# KeyBoard-RP2040_P1.net
KiCad netlist of a schematic drawn in Altium Designer
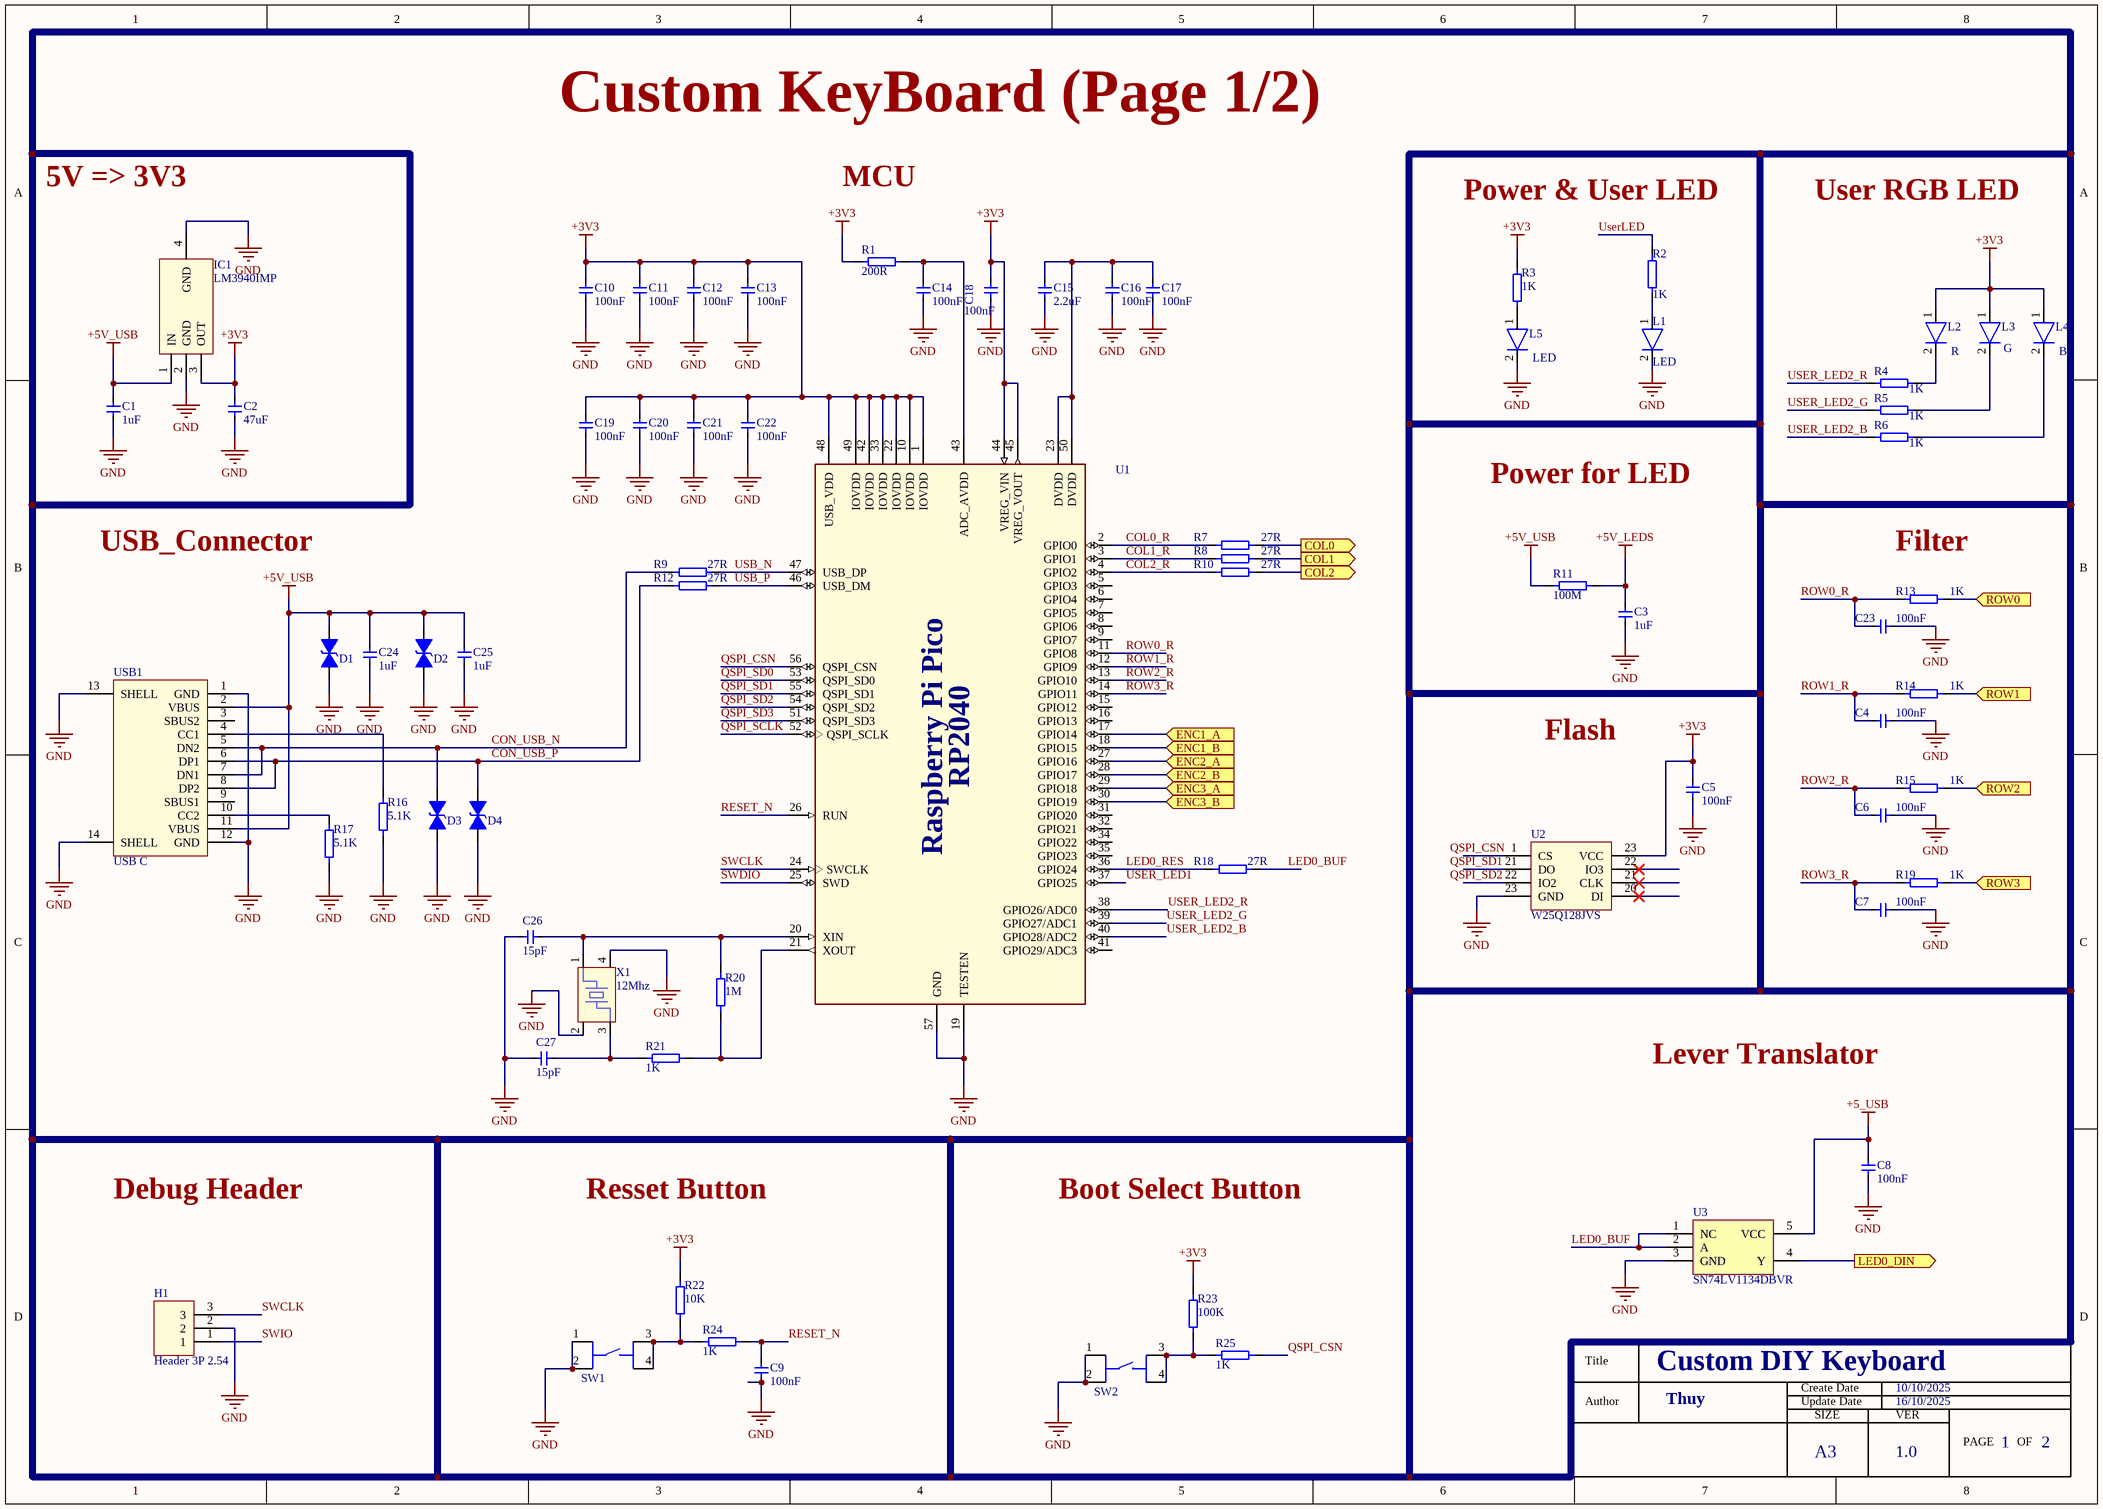
[diagram p0: KeyBoard-RP2040_P1.SchDoc]

(export (version "E")
  (design (tool "Eeschema 10.0.6"))
  (components
    (comp (ref "C1")
      (value "1uF")
      (footprint "C 0.79 0.54")
      (description "SMD 0402")
      (libsource (lib "SCHLib") (part "CAP 1uF"))
    )
    (comp (ref "C2")
      (value "47uF")
      (footprint "C 1.485 1.728")
      (description "SMD")
      (libsource (lib "SCHLib") (part "CAP 47uF"))
    )
    (comp (ref "C3")
      (value "1uF")
      (footprint "C 0.79 0.54")
      (description "SMD 0402")
      (libsource (lib "SCHLib") (part "CAP 1uF"))
    )
    (comp (ref "C4")
      (value "100nF")
      (footprint "C 0.79 0.54")
      (description "SMD")
      (libsource (lib "SCHLib") (part "CAP 100nF"))
    )
    (comp (ref "C5")
      (value "100nF")
      (footprint "C 0.79 0.54")
      (description "SMD")
      (libsource (lib "SCHLib") (part "CAP 100nF"))
    )
    (comp (ref "C6")
      (value "100nF")
      (footprint "C 0.79 0.54")
      (description "SMD")
      (libsource (lib "SCHLib") (part "CAP 100nF"))
    )
    (comp (ref "C7")
      (value "100nF")
      (footprint "C 0.79 0.54")
      (description "SMD")
      (libsource (lib "SCHLib") (part "CAP 100nF"))
    )
    (comp (ref "C8")
      (value "100nF")
      (footprint "C 0.79 0.54")
      (description "SMD")
      (libsource (lib "SCHLib") (part "CAP 100nF"))
    )
    (comp (ref "C9")
      (value "100nF")
      (footprint "C 0.79 0.54")
      (description "SMD")
      (libsource (lib "SCHLib") (part "CAP 100nF"))
    )
    (comp (ref "C10")
      (value "100nF")
      (footprint "C 0.79 0.54")
      (description "SMD")
      (libsource (lib "SCHLib") (part "CAP 100nF"))
    )
    (comp (ref "C11")
      (value "100nF")
      (footprint "C 0.79 0.54")
      (description "SMD")
      (libsource (lib "SCHLib") (part "CAP 100nF"))
    )
    (comp (ref "C12")
      (value "100nF")
      (footprint "C 0.79 0.54")
      (description "SMD")
      (libsource (lib "SCHLib") (part "CAP 100nF"))
    )
    (comp (ref "C13")
      (value "100nF")
      (footprint "C 0.79 0.54")
      (description "SMD")
      (libsource (lib "SCHLib") (part "CAP 100nF"))
    )
    (comp (ref "C14")
      (value "100nF")
      (footprint "C 0.79 0.54")
      (description "SMD")
      (libsource (lib "SCHLib") (part "CAP 100nF"))
    )
    (comp (ref "C15")
      (value "2.2uF")
      (footprint "C 0.79 0.54")
      (description "SMD")
      (libsource (lib "SCHLib") (part "CAP 2.2uF"))
    )
    (comp (ref "C16")
      (value "100nF")
      (footprint "C 0.79 0.54")
      (description "SMD")
      (libsource (lib "SCHLib") (part "CAP 100nF"))
    )
    (comp (ref "C17")
      (value "100nF")
      (footprint "C 0.79 0.54")
      (description "SMD")
      (libsource (lib "SCHLib") (part "CAP 100nF"))
    )
    (comp (ref "C18")
      (value "100nF")
      (footprint "C 0.79 0.54")
      (description "SMD")
      (libsource (lib "SCHLib") (part "CAP 100nF"))
    )
    (comp (ref "C19")
      (value "100nF")
      (footprint "C 0.79 0.54")
      (description "SMD")
      (libsource (lib "SCHLib") (part "CAP 100nF"))
    )
    (comp (ref "C20")
      (value "100nF")
      (footprint "C 0.79 0.54")
      (description "SMD")
      (libsource (lib "SCHLib") (part "CAP 100nF"))
    )
    (comp (ref "C21")
      (value "100nF")
      (footprint "C 0.79 0.54")
      (description "SMD")
      (libsource (lib "SCHLib") (part "CAP 100nF"))
    )
    (comp (ref "C22")
      (value "100nF")
      (footprint "C 0.79 0.54")
      (description "SMD")
      (libsource (lib "SCHLib") (part "CAP 100nF"))
    )
    (comp (ref "C23")
      (value "100nF")
      (footprint "C 0.79 0.54")
      (description "SMD")
      (libsource (lib "SCHLib") (part "CAP 100nF"))
    )
    (comp (ref "C24")
      (value "1uF")
      (footprint "C 0.79 0.54")
      (description "SMD 0402")
      (libsource (lib "SCHLib") (part "CAP 1uF"))
    )
    (comp (ref "C25")
      (value "1uF")
      (footprint "C 0.79 0.54")
      (description "SMD 0402")
      (libsource (lib "SCHLib") (part "CAP 1uF"))
    )
    (comp (ref "C26")
      (value "15pF")
      (footprint "C 0.79 0.54")
      (description "SMD")
      (libsource (lib "SCHLib") (part "CAP 15pF"))
    )
    (comp (ref "C27")
      (value "15pF")
      (footprint "C 0.79 0.54")
      (description "SMD")
      (libsource (lib "SCHLib") (part "CAP 15pF"))
    )
    (comp (ref "D1")
      (value "ESD GG0402052R542P")
      (footprint "D 0.6")
      (description "SMD")
      (libsource (lib "SCHLib") (part "ESD GG0402052R542P"))
    )
    (comp (ref "D2")
      (value "ESD GG0402052R542P")
      (footprint "D 0.6")
      (description "SMD")
      (libsource (lib "SCHLib") (part "ESD GG0402052R542P"))
    )
    (comp (ref "D3")
      (value "ESD GG0402052R542P")
      (footprint "D 0.6")
      (description "SMD")
      (libsource (lib "SCHLib") (part "ESD GG0402052R542P"))
    )
    (comp (ref "D4")
      (value "ESD GG0402052R542P")
      (footprint "D 0.6")
      (description "SMD")
      (libsource (lib "SCHLib") (part "ESD GG0402052R542P"))
    )
    (comp (ref "H1")
      (value "Header 3P 2.54")
      (footprint "Header 1x3")
      (description "THT")
      (libsource (lib "SCHLib") (part "Header 1x3"))
    )
    (comp (ref "IC1")
      (value "LM3940IMP")
      (footprint "LM39")
      (description "SOP ¦ 5v->3v3 ¦")
      (libsource (lib "SCHLib") (part "LM3940IMP"))
    )
    (comp (ref "L1") (value "LED") (footprint "LED") (libsource (lib "SCHLib") (part "LED2")))
    (comp (ref "L2") (value "R") (footprint "LED") (libsource (lib "SCHLib") (part "LED2")))
    (comp (ref "L3") (value "G") (footprint "LED") (libsource (lib "SCHLib") (part "LED2")))
    (comp (ref "L4") (value "B") (footprint "LED") (libsource (lib "SCHLib") (part "LED2")))
    (comp (ref "L5") (value "LED") (footprint "LED") (libsource (lib "SCHLib") (part "LED2")))
    (comp (ref "R1")
      (value "200R")
      (footprint "SMD 0.566 0.54")
      (description "SMD")
      (libsource (lib "SCHLib") (part "RES 200R"))
    )
    (comp (ref "R2")
      (value "1K")
      (footprint "SMD 0.566 0.54")
      (description "SMD")
      (libsource (lib "") (part "RES 1K_2"))
    )
    (comp (ref "R3")
      (value "1K")
      (footprint "SMD 0.566 0.54")
      (description "SMD")
      (libsource (lib "") (part "RES 1K_2"))
    )
    (comp (ref "R4")
      (value "1K")
      (footprint "SMD 0.566 0.54")
      (description "SMD")
      (libsource (lib "SCHLib") (part "RES 1K"))
    )
    (comp (ref "R5")
      (value "1K")
      (footprint "SMD 0.566 0.54")
      (description "SMD")
      (libsource (lib "SCHLib") (part "RES 1K"))
    )
    (comp (ref "R6")
      (value "1K")
      (footprint "SMD 0.566 0.54")
      (description "SMD")
      (libsource (lib "SCHLib") (part "RES 1K"))
    )
    (comp (ref "R7")
      (value "27R")
      (footprint "SMD 0.566 0.54")
      (description "SMD")
      (libsource (lib "SCHLib") (part "Res 27R"))
    )
    (comp (ref "R8")
      (value "27R")
      (footprint "SMD 0.566 0.54")
      (description "SMD")
      (libsource (lib "SCHLib") (part "Res 27R"))
    )
    (comp (ref "R9")
      (value "27R")
      (footprint "SMD 0.566 0.54")
      (description "SMD")
      (libsource (lib "SCHLib") (part "Res 27R"))
    )
    (comp (ref "R10")
      (value "27R")
      (footprint "SMD 0.566 0.54")
      (description "SMD")
      (libsource (lib "SCHLib") (part "Res 27R"))
    )
    (comp (ref "R11")
      (value "100M")
      (footprint "SMD 0.566 0.54")
      (description "SMD")
      (libsource (lib "SCHLib") (part "RES 100M"))
    )
    (comp (ref "R12")
      (value "27R")
      (footprint "SMD 0.566 0.54")
      (description "SMD")
      (libsource (lib "SCHLib") (part "Res 27R"))
    )
    (comp (ref "R13")
      (value "1K")
      (footprint "SMD 0.566 0.54")
      (description "SMD")
      (libsource (lib "") (part "RES 1K_1"))
    )
    (comp (ref "R14")
      (value "1K")
      (footprint "SMD 0.566 0.54")
      (description "SMD")
      (libsource (lib "") (part "RES 1K_1"))
    )
    (comp (ref "R15")
      (value "1K")
      (footprint "SMD 0.566 0.54")
      (description "SMD")
      (libsource (lib "") (part "RES 1K_1"))
    )
    (comp (ref "R16")
      (value "5.1K")
      (footprint "SMD 0.566 0.54")
      (description "SMD")
      (libsource (lib "SCHLib") (part "RES 5.1K"))
    )
    (comp (ref "R17")
      (value "5.1K")
      (footprint "SMD 0.566 0.54")
      (description "SMD")
      (libsource (lib "SCHLib") (part "RES 5.1K"))
    )
    (comp (ref "R18")
      (value "27R")
      (footprint "SMD 0.566 0.54")
      (description "SMD")
      (libsource (lib "SCHLib") (part "Res 27R"))
    )
    (comp (ref "R19")
      (value "1K")
      (footprint "SMD 0.566 0.54")
      (description "SMD")
      (libsource (lib "") (part "RES 1K_1"))
    )
    (comp (ref "R20")
      (value "1M")
      (footprint "SMD 0.566 0.54")
      (description "SMD")
      (libsource (lib "SCHLib") (part "RES 1M"))
    )
    (comp (ref "R21")
      (value "1K")
      (footprint "SMD 0.566 0.54")
      (description "SMD")
      (libsource (lib "") (part "RES 1K_1"))
    )
    (comp (ref "R22")
      (value "10K")
      (footprint "SMD 0.566 0.54")
      (description "SMD")
      (libsource (lib "SCHLib") (part "RES 10K"))
    )
    (comp (ref "R23")
      (value "100K")
      (footprint "SMD 0.566 0.54")
      (description "SMD")
      (libsource (lib "SCHLib") (part "RES 100K"))
    )
    (comp (ref "R24")
      (value "1K")
      (footprint "SMD 0.566 0.54")
      (description "SMD")
      (libsource (lib "") (part "RES 1K_1"))
    )
    (comp (ref "R25")
      (value "1K")
      (footprint "SMD 0.566 0.54")
      (description "SMD")
      (libsource (lib "") (part "RES 1K_1"))
    )
    (comp (ref "SW1")
      (value "BUTTON")
      (footprint "Button")
      (description "SMD")
      (libsource (lib "SCHLib") (part "BUTTON"))
    )
    (comp (ref "SW2")
      (value "BUTTON")
      (footprint "Button")
      (description "SMD")
      (libsource (lib "SCHLib") (part "BUTTON"))
    )
    (comp (ref "U1")
      (value "RP2040")
      (footprint "RP2040")
      (description "RP2040 chip for Raspberry Pi Pico - ARM® Cortex®-M0+ MCU 32-Bit")
      (libsource (lib "SCHLib") (part "Rasberry Pi Pico-RP2040"))
    )
    (comp (ref "U2")
      (value "W25Q128JVS")
      (footprint "W25Q128JVS")
      (description "SMD")
      (libsource (lib "SCHLib") (part "W25Q128JVS"))
    )
    (comp (ref "U3") (value "SN74LV1134DBVR") (libsource (lib "SCHLib") (part "SN74LV1134DBVR")))
    (comp (ref "USB1") (value "USB C") (footprint "USB-C") (libsource (lib "SCHLib") (part "USB C")))
    (comp (ref "X1")
      (value "12Mhz")
      (footprint "ABM8")
      (description "SMD")
      (libsource (lib "SCHLib") (part "Crystal ABM8-272-T3"))
    )
  )
  (nets
    (net (code "1") (name "+3V3") (class "Default")
      (node (ref "C10") (pin "2") (pinfunction "2_2") (pintype "passive"))
      (node (ref "C11") (pin "2") (pinfunction "2_2") (pintype "passive"))
      (node (ref "C12") (pin "2") (pinfunction "2_2") (pintype "passive"))
      (node (ref "C13") (pin "2") (pinfunction "2_2") (pintype "passive"))
      (node (ref "C18") (pin "2") (pinfunction "2_2") (pintype "passive"))
      (node (ref "C19") (pin "2") (pinfunction "2_2") (pintype "passive"))
      (node (ref "C2") (pin "2") (pinfunction "2_2") (pintype "passive"))
      (node (ref "C20") (pin "2") (pinfunction "2_2") (pintype "passive"))
      (node (ref "C21") (pin "2") (pinfunction "2_2") (pintype "passive"))
      (node (ref "C22") (pin "2") (pinfunction "2_2") (pintype "passive"))
      (node (ref "C5") (pin "2") (pinfunction "2_2") (pintype "passive"))
      (node (ref "IC1") (pin "3") (pinfunction "OUT_3") (pintype "passive"))
      (node (ref "L2") (pin "1") (pinfunction "1_1") (pintype "passive"))
      (node (ref "L3") (pin "1") (pinfunction "1_1") (pintype "passive"))
      (node (ref "L4") (pin "1") (pinfunction "1_1") (pintype "passive"))
      (node (ref "R1") (pin "1") (pinfunction "1_1") (pintype "passive"))
      (node (ref "R22") (pin "2") (pinfunction "2_2") (pintype "passive"))
      (node (ref "R23") (pin "2") (pinfunction "2_2") (pintype "passive"))
      (node (ref "R3") (pin "2") (pinfunction "2_2") (pintype "passive"))
      (node (ref "U1") (pin "1") (pinfunction "IOVDD_1") (pintype "power_in"))
      (node (ref "U1") (pin "10") (pinfunction "IOVDD_10") (pintype "power_in"))
      (node (ref "U1") (pin "22") (pinfunction "IOVDD_22") (pintype "power_in"))
      (node (ref "U1") (pin "33") (pinfunction "IOVDD_33") (pintype "power_in"))
      (node (ref "U1") (pin "42") (pinfunction "IOVDD_42") (pintype "power_in"))
      (node (ref "U1") (pin "44") (pinfunction "VREG_VIN_44") (pintype "input"))
      (node (ref "U1") (pin "45") (pinfunction "VREG_VOUT_45") (pintype "output"))
      (node (ref "U1") (pin "48") (pinfunction "USB_VDD_48") (pintype "power_in"))
      (node (ref "U1") (pin "49") (pinfunction "IOVDD_49") (pintype "power_in"))
      (node (ref "U2") (pin "23") (pinfunction "VCC_23") (pintype "passive"))
    )
    (net (code "2") (name "+5V_LEDS") (class "Default")
      (node (ref "C3") (pin "2") (pinfunction "2_2") (pintype "passive"))
      (node (ref "R11") (pin "2") (pinfunction "2_2") (pintype "passive"))
    )
    (net (code "3") (name "+5V_USB") (class "Default")
      (node (ref "C1") (pin "2") (pinfunction "2_2") (pintype "passive"))
      (node (ref "C24") (pin "2") (pinfunction "2_2") (pintype "passive"))
      (node (ref "C25") (pin "2") (pinfunction "2_2") (pintype "passive"))
      (node (ref "D1") (pin "2") (pinfunction "2_2") (pintype "passive"))
      (node (ref "D2") (pin "2") (pinfunction "2_2") (pintype "passive"))
      (node (ref "IC1") (pin "1") (pinfunction "IN_1") (pintype "passive"))
      (node (ref "R11") (pin "1") (pinfunction "1_1") (pintype "passive"))
      (node (ref "USB1") (pin "11") (pinfunction "VBUS_11") (pintype "passive"))
      (node (ref "USB1") (pin "2") (pinfunction "VBUS_2") (pintype "passive"))
    )
    (net (code "4") (name "+5_USB") (class "Default")
      (node (ref "C8") (pin "2") (pinfunction "2_2") (pintype "passive"))
      (node (ref "U3") (pin "5") (pinfunction "VCC_5") (pintype "passive"))
    )
    (net (code "5") (name "/COL0") (class "Default")
      (node (ref "R7") (pin "2") (pinfunction "2_2") (pintype "passive"))
    )
    (net (code "6") (name "/COL0_R") (class "Default")
      (node (ref "R7") (pin "1") (pinfunction "1_1") (pintype "passive"))
      (node (ref "U1") (pin "2") (pinfunction "GPIO0_2") (pintype "bidirectional"))
    )
    (net (code "7") (name "/COL1") (class "Default")
      (node (ref "R8") (pin "2") (pinfunction "2_2") (pintype "passive"))
    )
    (net (code "8") (name "/COL1_R") (class "Default")
      (node (ref "R8") (pin "1") (pinfunction "1_1") (pintype "passive"))
      (node (ref "U1") (pin "3") (pinfunction "GPIO1_3") (pintype "bidirectional"))
    )
    (net (code "9") (name "/COL2") (class "Default")
      (node (ref "R10") (pin "2") (pinfunction "2_2") (pintype "passive"))
    )
    (net (code "10") (name "/COL2_R") (class "Default")
      (node (ref "R10") (pin "1") (pinfunction "1_1") (pintype "passive"))
      (node (ref "U1") (pin "4") (pinfunction "GPIO2_4") (pintype "bidirectional"))
    )
    (net (code "11") (name "/CON_USB_N") (class "Default")
      (node (ref "D3") (pin "2") (pinfunction "2_2") (pintype "passive"))
      (node (ref "R9") (pin "1") (pinfunction "1_1") (pintype "passive"))
      (node (ref "USB1") (pin "5") (pinfunction "DN2_5") (pintype "passive"))
      (node (ref "USB1") (pin "7") (pinfunction "DN1_7") (pintype "passive"))
    )
    (net (code "12") (name "/CON_USB_P") (class "Default")
      (node (ref "D4") (pin "2") (pinfunction "2_2") (pintype "passive"))
      (node (ref "R12") (pin "1") (pinfunction "1_1") (pintype "passive"))
      (node (ref "USB1") (pin "6") (pinfunction "DP1_6") (pintype "passive"))
      (node (ref "USB1") (pin "8") (pinfunction "DP2_8") (pintype "passive"))
    )
    (net (code "13") (name "/ENC1_A") (class "Default")
      (node (ref "U1") (pin "17") (pinfunction "GPIO14_17") (pintype "bidirectional"))
    )
    (net (code "14") (name "/ENC1_B") (class "Default")
      (node (ref "U1") (pin "18") (pinfunction "GPIO15_18") (pintype "bidirectional"))
    )
    (net (code "15") (name "/ENC2_A") (class "Default")
      (node (ref "U1") (pin "27") (pinfunction "GPIO16_27") (pintype "bidirectional"))
    )
    (net (code "16") (name "/ENC2_B") (class "Default")
      (node (ref "U1") (pin "28") (pinfunction "GPIO17_28") (pintype "bidirectional"))
    )
    (net (code "17") (name "/ENC3_A") (class "Default")
      (node (ref "U1") (pin "29") (pinfunction "GPIO18_29") (pintype "bidirectional"))
    )
    (net (code "18") (name "/ENC3_B") (class "Default")
      (node (ref "U1") (pin "30") (pinfunction "GPIO19_30") (pintype "bidirectional"))
    )
    (net (code "19") (name "/LED0_BUF") (class "Default")
      (node (ref "R18") (pin "2") (pinfunction "2_2") (pintype "passive"))
      (node (ref "U3") (pin "1") (pinfunction "NC_1") (pintype "passive"))
      (node (ref "U3") (pin "2") (pinfunction "A_2") (pintype "passive"))
    )
    (net (code "20") (name "/LED0_DIN") (class "Default")
      (node (ref "U3") (pin "4") (pinfunction "Y_4") (pintype "passive"))
    )
    (net (code "21") (name "/LED0_RES") (class "Default")
      (node (ref "R18") (pin "1") (pinfunction "1_1") (pintype "passive"))
      (node (ref "U1") (pin "36") (pinfunction "GPIO24_36") (pintype "bidirectional"))
    )
    (net (code "22") (name "/QSPI_CSN") (class "Default")
      (node (ref "R25") (pin "2") (pinfunction "2_2") (pintype "passive"))
      (node (ref "U1") (pin "56") (pinfunction "QSPI_CSN_56") (pintype "bidirectional"))
    )
    (net (code "23") (name "/QSPI_SCLK") (class "Default")
      (node (ref "U1") (pin "52") (pinfunction "QSPI_SCLK_52") (pintype "bidirectional"))
    )
    (net (code "24") (name "/QSPI_SD0") (class "Default")
      (node (ref "U1") (pin "53") (pinfunction "QSPI_SD0_53") (pintype "bidirectional"))
    )
    (net (code "25") (name "/QSPI_SD1") (class "Default")
      (node (ref "U1") (pin "55") (pinfunction "QSPI_SD1_55") (pintype "bidirectional"))
    )
    (net (code "26") (name "/QSPI_SD2") (class "Default")
      (node (ref "U1") (pin "54") (pinfunction "QSPI_SD2_54") (pintype "bidirectional"))
    )
    (net (code "27") (name "/QSPI_SD3") (class "Default")
      (node (ref "U1") (pin "51") (pinfunction "QSPI_SD3_51") (pintype "bidirectional"))
    )
    (net (code "28") (name "/RESET_N") (class "Default")
      (node (ref "C9") (pin "2") (pinfunction "2_2") (pintype "passive"))
      (node (ref "R24") (pin "2") (pinfunction "2_2") (pintype "passive"))
      (node (ref "U1") (pin "26") (pinfunction "RUN_26") (pintype "input"))
    )
    (net (code "29") (name "/ROW0") (class "Default")
      (node (ref "R13") (pin "2") (pinfunction "2_2") (pintype "passive"))
    )
    (net (code "30") (name "/ROW0_R") (class "Default")
      (node (ref "C23") (pin "2") (pinfunction "2_2") (pintype "passive"))
      (node (ref "R13") (pin "1") (pinfunction "1_1") (pintype "passive"))
      (node (ref "U1") (pin "11") (pinfunction "GPIO8_11") (pintype "bidirectional"))
    )
    (net (code "31") (name "/ROW1") (class "Default")
      (node (ref "R14") (pin "2") (pinfunction "2_2") (pintype "passive"))
    )
    (net (code "32") (name "/ROW1_R") (class "Default")
      (node (ref "C4") (pin "2") (pinfunction "2_2") (pintype "passive"))
      (node (ref "R14") (pin "1") (pinfunction "1_1") (pintype "passive"))
      (node (ref "U1") (pin "12") (pinfunction "GPIO9_12") (pintype "bidirectional"))
    )
    (net (code "33") (name "/ROW2") (class "Default")
      (node (ref "R15") (pin "2") (pinfunction "2_2") (pintype "passive"))
    )
    (net (code "34") (name "/ROW2_R") (class "Default")
      (node (ref "C6") (pin "2") (pinfunction "2_2") (pintype "passive"))
      (node (ref "R15") (pin "1") (pinfunction "1_1") (pintype "passive"))
      (node (ref "U1") (pin "13") (pinfunction "GPIO10_13") (pintype "bidirectional"))
    )
    (net (code "35") (name "/ROW3") (class "Default")
      (node (ref "R19") (pin "2") (pinfunction "2_2") (pintype "passive"))
    )
    (net (code "36") (name "/ROW3_R") (class "Default")
      (node (ref "C7") (pin "2") (pinfunction "2_2") (pintype "passive"))
      (node (ref "R19") (pin "1") (pinfunction "1_1") (pintype "passive"))
      (node (ref "U1") (pin "14") (pinfunction "GPIO11_14") (pintype "bidirectional"))
    )
    (net (code "37") (name "/SWCLK") (class "Default")
      (node (ref "H1") (pin "3") (pinfunction "3_3") (pintype "passive"))
      (node (ref "U1") (pin "24") (pinfunction "SWCLK_24") (pintype "input"))
    )
    (net (code "38") (name "/SWDIO") (class "Default")
      (node (ref "U1") (pin "25") (pinfunction "SWD_25") (pintype "bidirectional"))
    )
    (net (code "39") (name "/SWIO") (class "Default")
      (node (ref "H1") (pin "1") (pinfunction "1_1") (pintype "passive"))
    )
    (net (code "40") (name "/USB_N") (class "Default")
      (node (ref "R9") (pin "2") (pinfunction "2_2") (pintype "passive"))
      (node (ref "U1") (pin "47") (pinfunction "USB_DP_47") (pintype "bidirectional"))
    )
    (net (code "41") (name "/USB_P") (class "Default")
      (node (ref "R12") (pin "2") (pinfunction "2_2") (pintype "passive"))
      (node (ref "U1") (pin "46") (pinfunction "USB_DM_46") (pintype "bidirectional"))
    )
    (net (code "42") (name "/USER_LED1") (class "Default")
      (node (ref "U1") (pin "37") (pinfunction "GPIO25_37") (pintype "bidirectional"))
    )
    (net (code "43") (name "/USER_LED2_B") (class "Default")
      (node (ref "R6") (pin "2") (pinfunction "2_2") (pintype "passive"))
      (node (ref "U1") (pin "40") (pinfunction "GPIO28/ADC2_40") (pintype "bidirectional"))
    )
    (net (code "44") (name "/USER_LED2_G") (class "Default")
      (node (ref "R5") (pin "2") (pinfunction "2_2") (pintype "passive"))
      (node (ref "U1") (pin "39") (pinfunction "GPIO27/ADC1_39") (pintype "bidirectional"))
    )
    (net (code "45") (name "/USER_LED2_R") (class "Default")
      (node (ref "R4") (pin "2") (pinfunction "2_2") (pintype "passive"))
      (node (ref "U1") (pin "38") (pinfunction "GPIO26/ADC0_38") (pintype "bidirectional"))
    )
    (net (code "46") (name "/UserLED") (class "Default")
      (node (ref "R2") (pin "2") (pinfunction "2_2") (pintype "passive"))
    )
    (net (code "47") (name "GND") (class "Default")
      (node (ref "C1") (pin "1") (pinfunction "1_1") (pintype "passive"))
      (node (ref "C10") (pin "1") (pinfunction "1_1") (pintype "passive"))
      (node (ref "C11") (pin "1") (pinfunction "1_1") (pintype "passive"))
      (node (ref "C12") (pin "1") (pinfunction "1_1") (pintype "passive"))
      (node (ref "C13") (pin "1") (pinfunction "1_1") (pintype "passive"))
      (node (ref "C14") (pin "1") (pinfunction "1_1") (pintype "passive"))
      (node (ref "C15") (pin "1") (pinfunction "1_1") (pintype "passive"))
      (node (ref "C16") (pin "1") (pinfunction "1_1") (pintype "passive"))
      (node (ref "C17") (pin "1") (pinfunction "1_1") (pintype "passive"))
      (node (ref "C18") (pin "1") (pinfunction "1_1") (pintype "passive"))
      (node (ref "C19") (pin "1") (pinfunction "1_1") (pintype "passive"))
      (node (ref "C2") (pin "1") (pinfunction "1_1") (pintype "passive"))
      (node (ref "C20") (pin "1") (pinfunction "1_1") (pintype "passive"))
      (node (ref "C21") (pin "1") (pinfunction "1_1") (pintype "passive"))
      (node (ref "C22") (pin "1") (pinfunction "1_1") (pintype "passive"))
      (node (ref "C23") (pin "1") (pinfunction "1_1") (pintype "passive"))
      (node (ref "C24") (pin "1") (pinfunction "1_1") (pintype "passive"))
      (node (ref "C25") (pin "1") (pinfunction "1_1") (pintype "passive"))
      (node (ref "C26") (pin "1") (pinfunction "1_1") (pintype "passive"))
      (node (ref "C27") (pin "1") (pinfunction "1_1") (pintype "passive"))
      (node (ref "C3") (pin "1") (pinfunction "1_1") (pintype "passive"))
      (node (ref "C4") (pin "1") (pinfunction "1_1") (pintype "passive"))
      (node (ref "C5") (pin "1") (pinfunction "1_1") (pintype "passive"))
      (node (ref "C6") (pin "1") (pinfunction "1_1") (pintype "passive"))
      (node (ref "C7") (pin "1") (pinfunction "1_1") (pintype "passive"))
      (node (ref "C8") (pin "1") (pinfunction "1_1") (pintype "passive"))
      (node (ref "C9") (pin "1") (pinfunction "1_1") (pintype "passive"))
      (node (ref "D1") (pin "1") (pinfunction "1_1") (pintype "passive"))
      (node (ref "D2") (pin "1") (pinfunction "1_1") (pintype "passive"))
      (node (ref "D3") (pin "1") (pinfunction "1_1") (pintype "passive"))
      (node (ref "D4") (pin "1") (pinfunction "1_1") (pintype "passive"))
      (node (ref "H1") (pin "2") (pinfunction "2_2") (pintype "passive"))
      (node (ref "IC1") (pin "2") (pinfunction "GND_2") (pintype "passive"))
      (node (ref "IC1") (pin "4") (pinfunction "GND_4") (pintype "passive"))
      (node (ref "L1") (pin "2") (pinfunction "2_2") (pintype "passive"))
      (node (ref "L5") (pin "2") (pinfunction "2_2") (pintype "passive"))
      (node (ref "R16") (pin "1") (pinfunction "1_1") (pintype "passive"))
      (node (ref "R17") (pin "1") (pinfunction "1_1") (pintype "passive"))
      (node (ref "SW1") (pin "1") (pinfunction "1_1") (pintype "passive"))
      (node (ref "SW1") (pin "2") (pinfunction "2_2") (pintype "passive"))
      (node (ref "SW2") (pin "1") (pinfunction "1_1") (pintype "passive"))
      (node (ref "SW2") (pin "2") (pinfunction "2_2") (pintype "passive"))
      (node (ref "U1") (pin "19") (pinfunction "TESTEN_19") (pintype "passive"))
      (node (ref "U1") (pin "57") (pinfunction "GND_57") (pintype "power_in"))
      (node (ref "U2") (pin "23") (pinfunction "GND_23") (pintype "passive"))
      (node (ref "U3") (pin "3") (pinfunction "GND_3") (pintype "passive"))
      (node (ref "USB1") (pin "1") (pinfunction "GND_1") (pintype "passive"))
      (node (ref "USB1") (pin "12") (pinfunction "GND_12") (pintype "passive"))
      (node (ref "USB1") (pin "13") (pinfunction "SHELL_13") (pintype "passive"))
      (node (ref "USB1") (pin "14") (pinfunction "SHELL_14") (pintype "passive"))
      (node (ref "X1") (pin "2") (pinfunction "GND_2") (pintype "passive"))
      (node (ref "X1") (pin "4") (pinfunction "GND_4") (pintype "passive"))
    )
    (net (code "48") (name "Net-(C15-Pad2)") (class "Default")
      (node (ref "C15") (pin "2") (pinfunction "2_2") (pintype "passive"))
      (node (ref "C16") (pin "2") (pinfunction "2_2") (pintype "passive"))
      (node (ref "C17") (pin "2") (pinfunction "2_2") (pintype "passive"))
      (node (ref "U1") (pin "23") (pinfunction "DVDD_23") (pintype "power_in"))
      (node (ref "U1") (pin "50") (pinfunction "DVDD_50") (pintype "power_in"))
    )
    (net (code "49") (name "Net-(C27-Pad2)") (class "Default")
      (node (ref "C27") (pin "2") (pinfunction "2_2") (pintype "passive"))
      (node (ref "R21") (pin "1") (pinfunction "1_1") (pintype "passive"))
      (node (ref "X1") (pin "3") (pinfunction "3_3") (pintype "passive"))
    )
    (net (code "50") (name "Net-(L1-Pad1)") (class "Default")
      (node (ref "L1") (pin "1") (pinfunction "1_1") (pintype "passive"))
      (node (ref "R2") (pin "1") (pinfunction "1_1") (pintype "passive"))
    )
    (net (code "51") (name "Net-(L2-Pad2)") (class "Default")
      (node (ref "L2") (pin "2") (pinfunction "2_2") (pintype "passive"))
      (node (ref "R4") (pin "1") (pinfunction "1_1") (pintype "passive"))
    )
    (net (code "52") (name "Net-(L3-Pad2)") (class "Default")
      (node (ref "L3") (pin "2") (pinfunction "2_2") (pintype "passive"))
      (node (ref "R5") (pin "1") (pinfunction "1_1") (pintype "passive"))
    )
    (net (code "53") (name "Net-(L4-Pad2)") (class "Default")
      (node (ref "L4") (pin "2") (pinfunction "2_2") (pintype "passive"))
      (node (ref "R6") (pin "1") (pinfunction "1_1") (pintype "passive"))
    )
    (net (code "54") (name "Net-(L5-Pad1)") (class "Default")
      (node (ref "L5") (pin "1") (pinfunction "1_1") (pintype "passive"))
      (node (ref "R3") (pin "1") (pinfunction "1_1") (pintype "passive"))
    )
    (net (code "55") (name "Net-(R22-Pad1)") (class "Default")
      (node (ref "R22") (pin "1") (pinfunction "1_1") (pintype "passive"))
      (node (ref "R24") (pin "1") (pinfunction "1_1") (pintype "passive"))
      (node (ref "SW1") (pin "3") (pinfunction "3_3") (pintype "passive"))
      (node (ref "SW1") (pin "4") (pinfunction "4_4") (pintype "passive"))
    )
    (net (code "56") (name "Net-(R23-Pad1)") (class "Default")
      (node (ref "R23") (pin "1") (pinfunction "1_1") (pintype "passive"))
      (node (ref "R25") (pin "1") (pinfunction "1_1") (pintype "passive"))
      (node (ref "SW2") (pin "3") (pinfunction "3_3") (pintype "passive"))
      (node (ref "SW2") (pin "4") (pinfunction "4_4") (pintype "passive"))
    )
    (net (code "57") (name "Net-(U1-ADC_AVDD)") (class "Default")
      (node (ref "C14") (pin "2") (pinfunction "2_2") (pintype "passive"))
      (node (ref "R1") (pin "2") (pinfunction "2_2") (pintype "passive"))
      (node (ref "U1") (pin "43") (pinfunction "ADC_AVDD_43") (pintype "power_in"))
    )
    (net (code "58") (name "Net-(U1-XIN)") (class "Default")
      (node (ref "C26") (pin "2") (pinfunction "2_2") (pintype "passive"))
      (node (ref "R20") (pin "2") (pinfunction "2_2") (pintype "passive"))
      (node (ref "U1") (pin "20") (pinfunction "XIN_20") (pintype "input"))
      (node (ref "X1") (pin "1") (pinfunction "1_1") (pintype "passive"))
    )
    (net (code "59") (name "Net-(U1-XOUT)") (class "Default")
      (node (ref "R20") (pin "1") (pinfunction "1_1") (pintype "passive"))
      (node (ref "R21") (pin "2") (pinfunction "2_2") (pintype "passive"))
      (node (ref "U1") (pin "21") (pinfunction "XOUT_21") (pintype "output"))
    )
    (net (code "60") (name "Net-(USB1-CC1)") (class "Default")
      (node (ref "R16") (pin "2") (pinfunction "2_2") (pintype "passive"))
      (node (ref "USB1") (pin "4") (pinfunction "CC1_4") (pintype "passive"))
    )
    (net (code "61") (name "Net-(USB1-CC2)") (class "Default")
      (node (ref "R17") (pin "2") (pinfunction "2_2") (pintype "passive"))
      (node (ref "USB1") (pin "10") (pinfunction "CC2_10") (pintype "passive"))
    )
    (net (code "62") (name "unconnected-(U1-GPIO3-Pad5)") (class "Default")
      (node (ref "U1") (pin "5") (pinfunction "GPIO3_5") (pintype "bidirectional"))
    )
    (net (code "63") (name "unconnected-(U1-GPIO4-Pad6)") (class "Default")
      (node (ref "U1") (pin "6") (pinfunction "GPIO4_6") (pintype "bidirectional"))
    )
    (net (code "64") (name "unconnected-(U1-GPIO5-Pad7)") (class "Default")
      (node (ref "U1") (pin "7") (pinfunction "GPIO5_7") (pintype "bidirectional"))
    )
    (net (code "65") (name "unconnected-(U1-GPIO6-Pad8)") (class "Default")
      (node (ref "U1") (pin "8") (pinfunction "GPIO6_8") (pintype "bidirectional"))
    )
    (net (code "66") (name "unconnected-(U1-GPIO7-Pad9)") (class "Default")
      (node (ref "U1") (pin "9") (pinfunction "GPIO7_9") (pintype "bidirectional"))
    )
    (net (code "67") (name "unconnected-(U1-GPIO12-Pad15)") (class "Default")
      (node (ref "U1") (pin "15") (pinfunction "GPIO12_15") (pintype "bidirectional"))
    )
    (net (code "68") (name "unconnected-(U1-GPIO13-Pad16)") (class "Default")
      (node (ref "U1") (pin "16") (pinfunction "GPIO13_16") (pintype "bidirectional"))
    )
    (net (code "69") (name "unconnected-(U1-GPIO20-Pad31)") (class "Default")
      (node (ref "U1") (pin "31") (pinfunction "GPIO20_31") (pintype "bidirectional"))
    )
    (net (code "70") (name "unconnected-(U1-GPIO21-Pad32)") (class "Default")
      (node (ref "U1") (pin "32") (pinfunction "GPIO21_32") (pintype "bidirectional"))
    )
    (net (code "71") (name "unconnected-(U1-GPIO22-Pad34)") (class "Default")
      (node (ref "U1") (pin "34") (pinfunction "GPIO22_34") (pintype "bidirectional"))
    )
    (net (code "72") (name "unconnected-(U1-GPIO23-Pad35)") (class "Default")
      (node (ref "U1") (pin "35") (pinfunction "GPIO23_35") (pintype "bidirectional"))
    )
    (net (code "73") (name "unconnected-(U1-GPIO29{slash}ADC3-Pad41)") (class "Default")
      (node (ref "U1") (pin "41") (pinfunction "GPIO29/ADC3_41") (pintype "bidirectional"))
    )
    (net (code "74") (name "unconnected-(U2-CLK-Pad21)") (class "Default")
      (node (ref "U2") (pin "21") (pinfunction "CLK_21") (pintype "passive+no_connect"))
    )
    (net (code "75") (name "unconnected-(U2-CS-Pad1)") (class "Default")
      (node (ref "U2") (pin "1") (pinfunction "CS_1") (pintype "passive"))
    )
    (net (code "76") (name "unconnected-(U2-DI-Pad20)") (class "Default")
      (node (ref "U2") (pin "20") (pinfunction "DI_20") (pintype "passive+no_connect"))
    )
    (net (code "77") (name "unconnected-(U2-DO-Pad21)") (class "Default")
      (node (ref "U2") (pin "21") (pinfunction "DO_21") (pintype "passive"))
    )
    (net (code "78") (name "unconnected-(U2-IO2-Pad22)") (class "Default")
      (node (ref "U2") (pin "22") (pinfunction "IO2_22") (pintype "passive"))
    )
    (net (code "79") (name "unconnected-(U2-IO3-Pad22)") (class "Default")
      (node (ref "U2") (pin "22") (pinfunction "IO3_22") (pintype "passive+no_connect"))
    )
    (net (code "80") (name "unconnected-(USB1-SBUS1-Pad9)") (class "Default")
      (node (ref "USB1") (pin "9") (pinfunction "SBUS1_9") (pintype "passive"))
    )
    (net (code "81") (name "unconnected-(USB1-SBUS2-Pad3)") (class "Default")
      (node (ref "USB1") (pin "3") (pinfunction "SBUS2_3") (pintype "passive"))
    )
  )
)
